# MCX_Mezzanine.net
KiCad netlist of a schematic drawn in Altium Designer
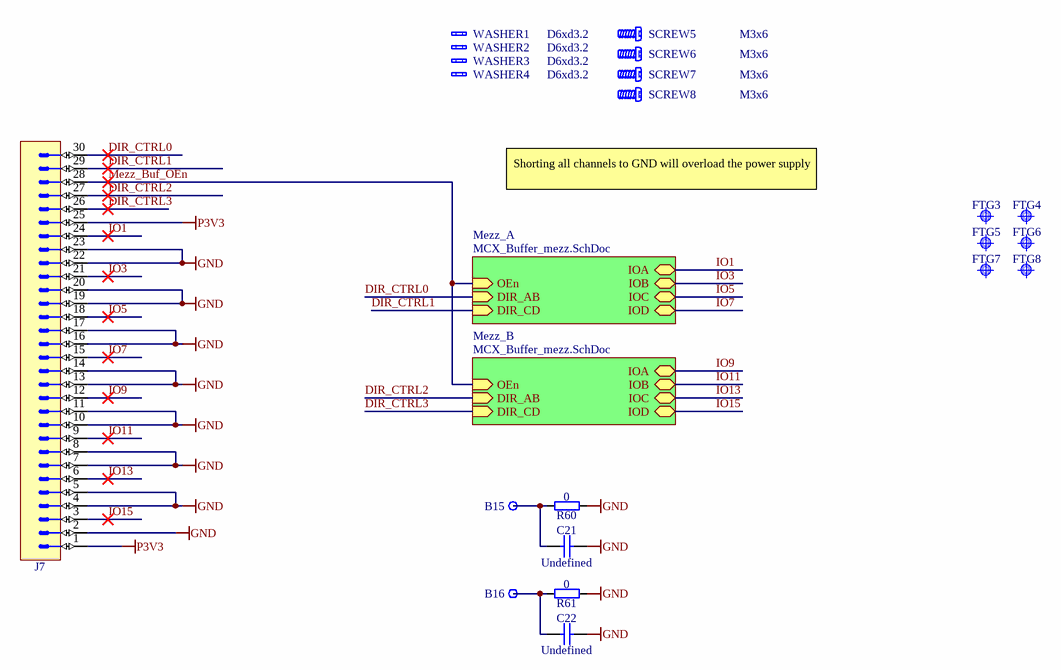
[diagram p0: MCX_Mezzanine.SchDoc]

(export (version "E")
  (design (tool "Eeschema 10.0.6"))
  (components
    (comp (ref "B15")
      (value "Plated Hole")
      (footprint "MTG270_500")
      (description "Single Terminal Socket")
      (fields (field (name "PART NUMBER") "PLATED_HOLE2.7_PAD5.0") (field (name "AUTHOR") "CERN DEM JMW"))
      (libsource (lib "Eletro-mechanical") (part "Single Terminal Socket"))
    )
    (comp (ref "B16")
      (value "Plated Hole")
      (footprint "MTG270_500")
      (description "Single Terminal Socket")
      (fields (field (name "PART NUMBER") "PLATED_HOLE2.7_PAD5.0") (field (name "AUTHOR") "CERN DEM JMW"))
      (libsource (lib "Eletro-mechanical") (part "Single Terminal Socket"))
    )
    (comp (ref "C21")
      (value "Undefined")
      (footprint "CAPC2012X135N")
      (description "Non-polarised capacitor")
      (fields (field (name "PART NUMBER") "CC0805_NO-VALUE") (field (name "AUTHOR") "CERN DEM JLC"))
      (libsource (lib "Capacitors") (part "Capacitor - non polarized"))
    )
    (comp (ref "C22")
      (value "Undefined")
      (footprint "CAPC2012X135N")
      (description "Non-polarised capacitor")
      (fields (field (name "PART NUMBER") "CC0805_NO-VALUE") (field (name "AUTHOR") "CERN DEM JLC"))
      (libsource (lib "Capacitors") (part "Capacitor - non polarized"))
    )
    (comp (ref "FTG3")
      (value "Use only in PCB")
      (footprint "FIDUCIAL_TOP_S100-200")
      (description "Fiducial Target")
      (fields (field (name "PART NUMBER") "FIDUCIAL_TARGET_S100-200") (field (name "AUTHOR") "CERN DEM JLC"))
      (libsource (lib "Eletro-mechanical") (part "Fiducial Target"))
    )
    (comp (ref "FTG4")
      (value "Use only in PCB")
      (footprint "FIDUCIAL_TOP_C100-200")
      (description "Fiducial Target")
      (fields (field (name "PART NUMBER") "FIDUCIAL_TARGET_C100-200") (field (name "AUTHOR") "CERN DEM JLC"))
      (libsource (lib "Eletro-mechanical") (part "Fiducial Target"))
    )
    (comp (ref "FTG5")
      (value "Use only in PCB")
      (footprint "FIDUCIAL_TOP_S100-200")
      (description "Fiducial Target")
      (fields (field (name "PART NUMBER") "FIDUCIAL_TARGET_S100-200") (field (name "AUTHOR") "CERN DEM JLC"))
      (libsource (lib "Eletro-mechanical") (part "Fiducial Target"))
    )
    (comp (ref "FTG6")
      (value "Use only in PCB")
      (footprint "FIDUCIAL_TOP_C100-200")
      (description "Fiducial Target")
      (fields (field (name "PART NUMBER") "FIDUCIAL_TARGET_C100-200") (field (name "AUTHOR") "CERN DEM JLC"))
      (libsource (lib "Eletro-mechanical") (part "Fiducial Target"))
    )
    (comp (ref "FTG7")
      (value "Use only in PCB")
      (footprint "FIDUCIAL_TOP_C100-200")
      (description "Fiducial Target")
      (fields (field (name "PART NUMBER") "FIDUCIAL_TARGET_C100-200") (field (name "AUTHOR") "CERN DEM JLC"))
      (libsource (lib "Eletro-mechanical") (part "Fiducial Target"))
    )
    (comp (ref "FTG8")
      (value "Use only in PCB")
      (footprint "FIDUCIAL_TOP_S100-200")
      (description "Fiducial Target")
      (fields (field (name "PART NUMBER") "FIDUCIAL_TARGET_S100-200") (field (name "AUTHOR") "CERN DEM JLC"))
      (libsource (lib "Eletro-mechanical") (part "Fiducial Target"))
    )
    (comp (ref "J7")
      (value "AMPMODU")
      (footprint "TYCO_1-215307-5")
      (description "Connector 2.54mm, 30 pin female, vertical, 7mm, AMPMODU HV-100/HV-190")
      (fields
        (field (name "PART NUMBER") "TYCO_1-215307-5")
        (field (name "MANUFACTURER") "TYCO ELECTRONICS")
        (field (name "AUTHOR") "GK")
      )
      (libsource (lib "LIBRARY_SCH") (part "CON_2x15_2.54_female_V_mirror"))
    )
    (comp (ref "R60")
      (value "0")
      (footprint "RESC1608X55N")
      (description "Resistor")
      (fields
        (field (name "PART NUMBER") "R0603_0R_JUMPER")
        (field (name "MANUFACTURER") "GENERIC")
        (field (name "AUTHOR") "CERN DEM JLC")
      )
      (libsource (lib "Resistors") (part "Resistor"))
    )
    (comp (ref "R61")
      (value "0")
      (footprint "RESC1608X55N")
      (description "Resistor")
      (fields
        (field (name "PART NUMBER") "R0603_0R_JUMPER")
        (field (name "MANUFACTURER") "GENERIC")
        (field (name "AUTHOR") "CERN DEM JLC")
      )
      (libsource (lib "Resistors") (part "Resistor"))
    )
    (comp (ref "SCREW5")
      (value "M3x6")
      (footprint "BOSSARD_BN5687-3061605_v")
      (description "Screw")
      (fields
        (field (name "PART NUMBER") "BOSSARD_BN5687-3061605_v")
        (field (name "MANUFACTURER") "BOSSARD")
        (field (name "AUTHOR") "CERN DEM JLC")
      )
      (libsource (lib "Eletro-mechanical") (part "Screw"))
    )
    (comp (ref "SCREW6")
      (value "M3x6")
      (footprint "BOSSARD_BN5687-3061605_v")
      (description "Screw")
      (fields
        (field (name "PART NUMBER") "BOSSARD_BN5687-3061605_v")
        (field (name "MANUFACTURER") "BOSSARD")
        (field (name "AUTHOR") "CERN DEM JLC")
      )
      (libsource (lib "Eletro-mechanical") (part "Screw"))
    )
    (comp (ref "SCREW7")
      (value "M3x6")
      (footprint "BOSSARD_BN5687-3061605_v")
      (description "Screw")
      (fields
        (field (name "PART NUMBER") "BOSSARD_BN5687-3061605_v")
        (field (name "MANUFACTURER") "BOSSARD")
        (field (name "AUTHOR") "CERN DEM JLC")
      )
      (libsource (lib "Eletro-mechanical") (part "Screw"))
    )
    (comp (ref "SCREW8")
      (value "M3x6")
      (footprint "BOSSARD_BN5687-3061605_v")
      (description "Screw")
      (fields
        (field (name "PART NUMBER") "BOSSARD_BN5687-3061605_v")
        (field (name "MANUFACTURER") "BOSSARD")
        (field (name "AUTHOR") "CERN DEM JLC")
      )
      (libsource (lib "Eletro-mechanical") (part "Screw"))
    )
    (comp (ref "WASHER1")
      (value "D6xd3.2")
      (footprint "BOSSARD_B3/6/0.3/BN1976_v")
      (description "Washer, M3x0.3x6")
      (fields
        (field (name "PART NUMBER") "BOSSARD_B3/6/0.3/BN1976")
        (field (name "MANUFACTURER") "BOSSARD")
        (field (name "AUTHOR") "GK")
      )
      (libsource (lib "Mechanical") (part "MECH_Washer_M3x0.3x6"))
    )
    (comp (ref "WASHER2")
      (value "D6xd3.2")
      (footprint "BOSSARD_B3/6/0.3/BN1976_v")
      (description "Washer, M3x0.3x6")
      (fields
        (field (name "PART NUMBER") "BOSSARD_B3/6/0.3/BN1976")
        (field (name "MANUFACTURER") "BOSSARD")
        (field (name "AUTHOR") "GK")
      )
      (libsource (lib "Mechanical") (part "MECH_Washer_M3x0.3x6"))
    )
    (comp (ref "WASHER3")
      (value "D6xd3.2")
      (footprint "BOSSARD_B3/6/0.3/BN1976_v")
      (description "Washer, M3x0.3x6")
      (fields
        (field (name "PART NUMBER") "BOSSARD_B3/6/0.3/BN1976")
        (field (name "MANUFACTURER") "BOSSARD")
        (field (name "AUTHOR") "GK")
      )
      (libsource (lib "Mechanical") (part "MECH_Washer_M3x0.3x6"))
    )
    (comp (ref "WASHER4")
      (value "D6xd3.2")
      (footprint "BOSSARD_B3/6/0.3/BN1976_v")
      (description "Washer, M3x0.3x6")
      (fields
        (field (name "PART NUMBER") "BOSSARD_B3/6/0.3/BN1976")
        (field (name "MANUFACTURER") "BOSSARD")
        (field (name "AUTHOR") "GK")
      )
      (libsource (lib "Mechanical") (part "MECH_Washer_M3x0.3x6"))
    )
  )
  (nets
    (net (code "1") (name "/DIR_CTRL0") (class "Default")
      (node (ref "J7") (pin "30") (pinfunction "30_30") (pintype "bidirectional"))
    )
    (net (code "2") (name "/DIR_CTRL1") (class "Default")
      (node (ref "J7") (pin "29") (pinfunction "29_29") (pintype "bidirectional"))
    )
    (net (code "3") (name "/DIR_CTRL2") (class "Default")
      (node (ref "J7") (pin "27") (pinfunction "27_27") (pintype "bidirectional"))
    )
    (net (code "4") (name "/DIR_CTRL3") (class "Default")
      (node (ref "J7") (pin "26") (pinfunction "26_26") (pintype "bidirectional"))
    )
    (net (code "5") (name "/IO1") (class "Default")
      (node (ref "J7") (pin "24") (pinfunction "24_24") (pintype "bidirectional"))
    )
    (net (code "6") (name "/IO3") (class "Default")
      (node (ref "J7") (pin "21") (pinfunction "21_21") (pintype "bidirectional"))
    )
    (net (code "7") (name "/IO5") (class "Default")
      (node (ref "J7") (pin "18") (pinfunction "18_18") (pintype "bidirectional"))
    )
    (net (code "8") (name "/IO7") (class "Default")
      (node (ref "J7") (pin "15") (pinfunction "15_15") (pintype "bidirectional"))
    )
    (net (code "9") (name "/IO9") (class "Default")
      (node (ref "J7") (pin "12") (pinfunction "12_12") (pintype "bidirectional"))
    )
    (net (code "10") (name "/IO11") (class "Default")
      (node (ref "J7") (pin "9") (pinfunction "9_9") (pintype "bidirectional"))
    )
    (net (code "11") (name "/IO13") (class "Default")
      (node (ref "J7") (pin "6") (pinfunction "6_6") (pintype "bidirectional"))
    )
    (net (code "12") (name "/IO15") (class "Default")
      (node (ref "J7") (pin "3") (pinfunction "3_3") (pintype "bidirectional"))
    )
    (net (code "14") (name "/OEn") (class "Default")
      (node (ref "J7") (pin "28") (pinfunction "28_28") (pintype "bidirectional"))
    )
    (net (code "15") (name "GND") (class "Default")
      (node (ref "C21") (pin "2") (pinfunction "2_2") (pintype "passive"))
      (node (ref "C22") (pin "2") (pinfunction "2_2") (pintype "passive"))
      (node (ref "J7") (pin "10") (pinfunction "10_10") (pintype "bidirectional"))
      (node (ref "J7") (pin "11") (pinfunction "11_11") (pintype "bidirectional"))
      (node (ref "J7") (pin "13") (pinfunction "13_13") (pintype "bidirectional"))
      (node (ref "J7") (pin "14") (pinfunction "14_14") (pintype "bidirectional"))
      (node (ref "J7") (pin "16") (pinfunction "16_16") (pintype "bidirectional"))
      (node (ref "J7") (pin "17") (pinfunction "17_17") (pintype "bidirectional"))
      (node (ref "J7") (pin "19") (pinfunction "19_19") (pintype "bidirectional"))
      (node (ref "J7") (pin "2") (pinfunction "2_2") (pintype "bidirectional"))
      (node (ref "J7") (pin "20") (pinfunction "20_20") (pintype "bidirectional"))
      (node (ref "J7") (pin "22") (pinfunction "22_22") (pintype "bidirectional"))
      (node (ref "J7") (pin "23") (pinfunction "23_23") (pintype "bidirectional"))
      (node (ref "J7") (pin "4") (pinfunction "4_4") (pintype "bidirectional"))
      (node (ref "J7") (pin "5") (pinfunction "5_5") (pintype "bidirectional"))
      (node (ref "J7") (pin "7") (pinfunction "7_7") (pintype "bidirectional"))
      (node (ref "J7") (pin "8") (pinfunction "8_8") (pintype "bidirectional"))
      (node (ref "R60") (pin "1") (pinfunction "1_1") (pintype "passive"))
      (node (ref "R61") (pin "1") (pinfunction "1_1") (pintype "passive"))
    )
    (net (code "16") (name "Net-(B15-Pad1)") (class "Default")
      (node (ref "B15") (pin "1") (pinfunction "1_1") (pintype "bidirectional"))
      (node (ref "C21") (pin "1") (pinfunction "1_1") (pintype "passive"))
      (node (ref "R60") (pin "2") (pinfunction "2_2") (pintype "passive"))
    )
    (net (code "17") (name "Net-(B16-Pad1)") (class "Default")
      (node (ref "B16") (pin "1") (pinfunction "1_1") (pintype "bidirectional"))
      (node (ref "C22") (pin "1") (pinfunction "1_1") (pintype "passive"))
      (node (ref "R61") (pin "2") (pinfunction "2_2") (pintype "passive"))
    )
    (net (code "18") (name "P3V3") (class "Default")
      (node (ref "J7") (pin "1") (pinfunction "1_1") (pintype "bidirectional"))
      (node (ref "J7") (pin "25") (pinfunction "25_25") (pintype "bidirectional"))
    )
  )
)
